# Top.net
KiCad netlist of a schematic drawn in Altium Designer
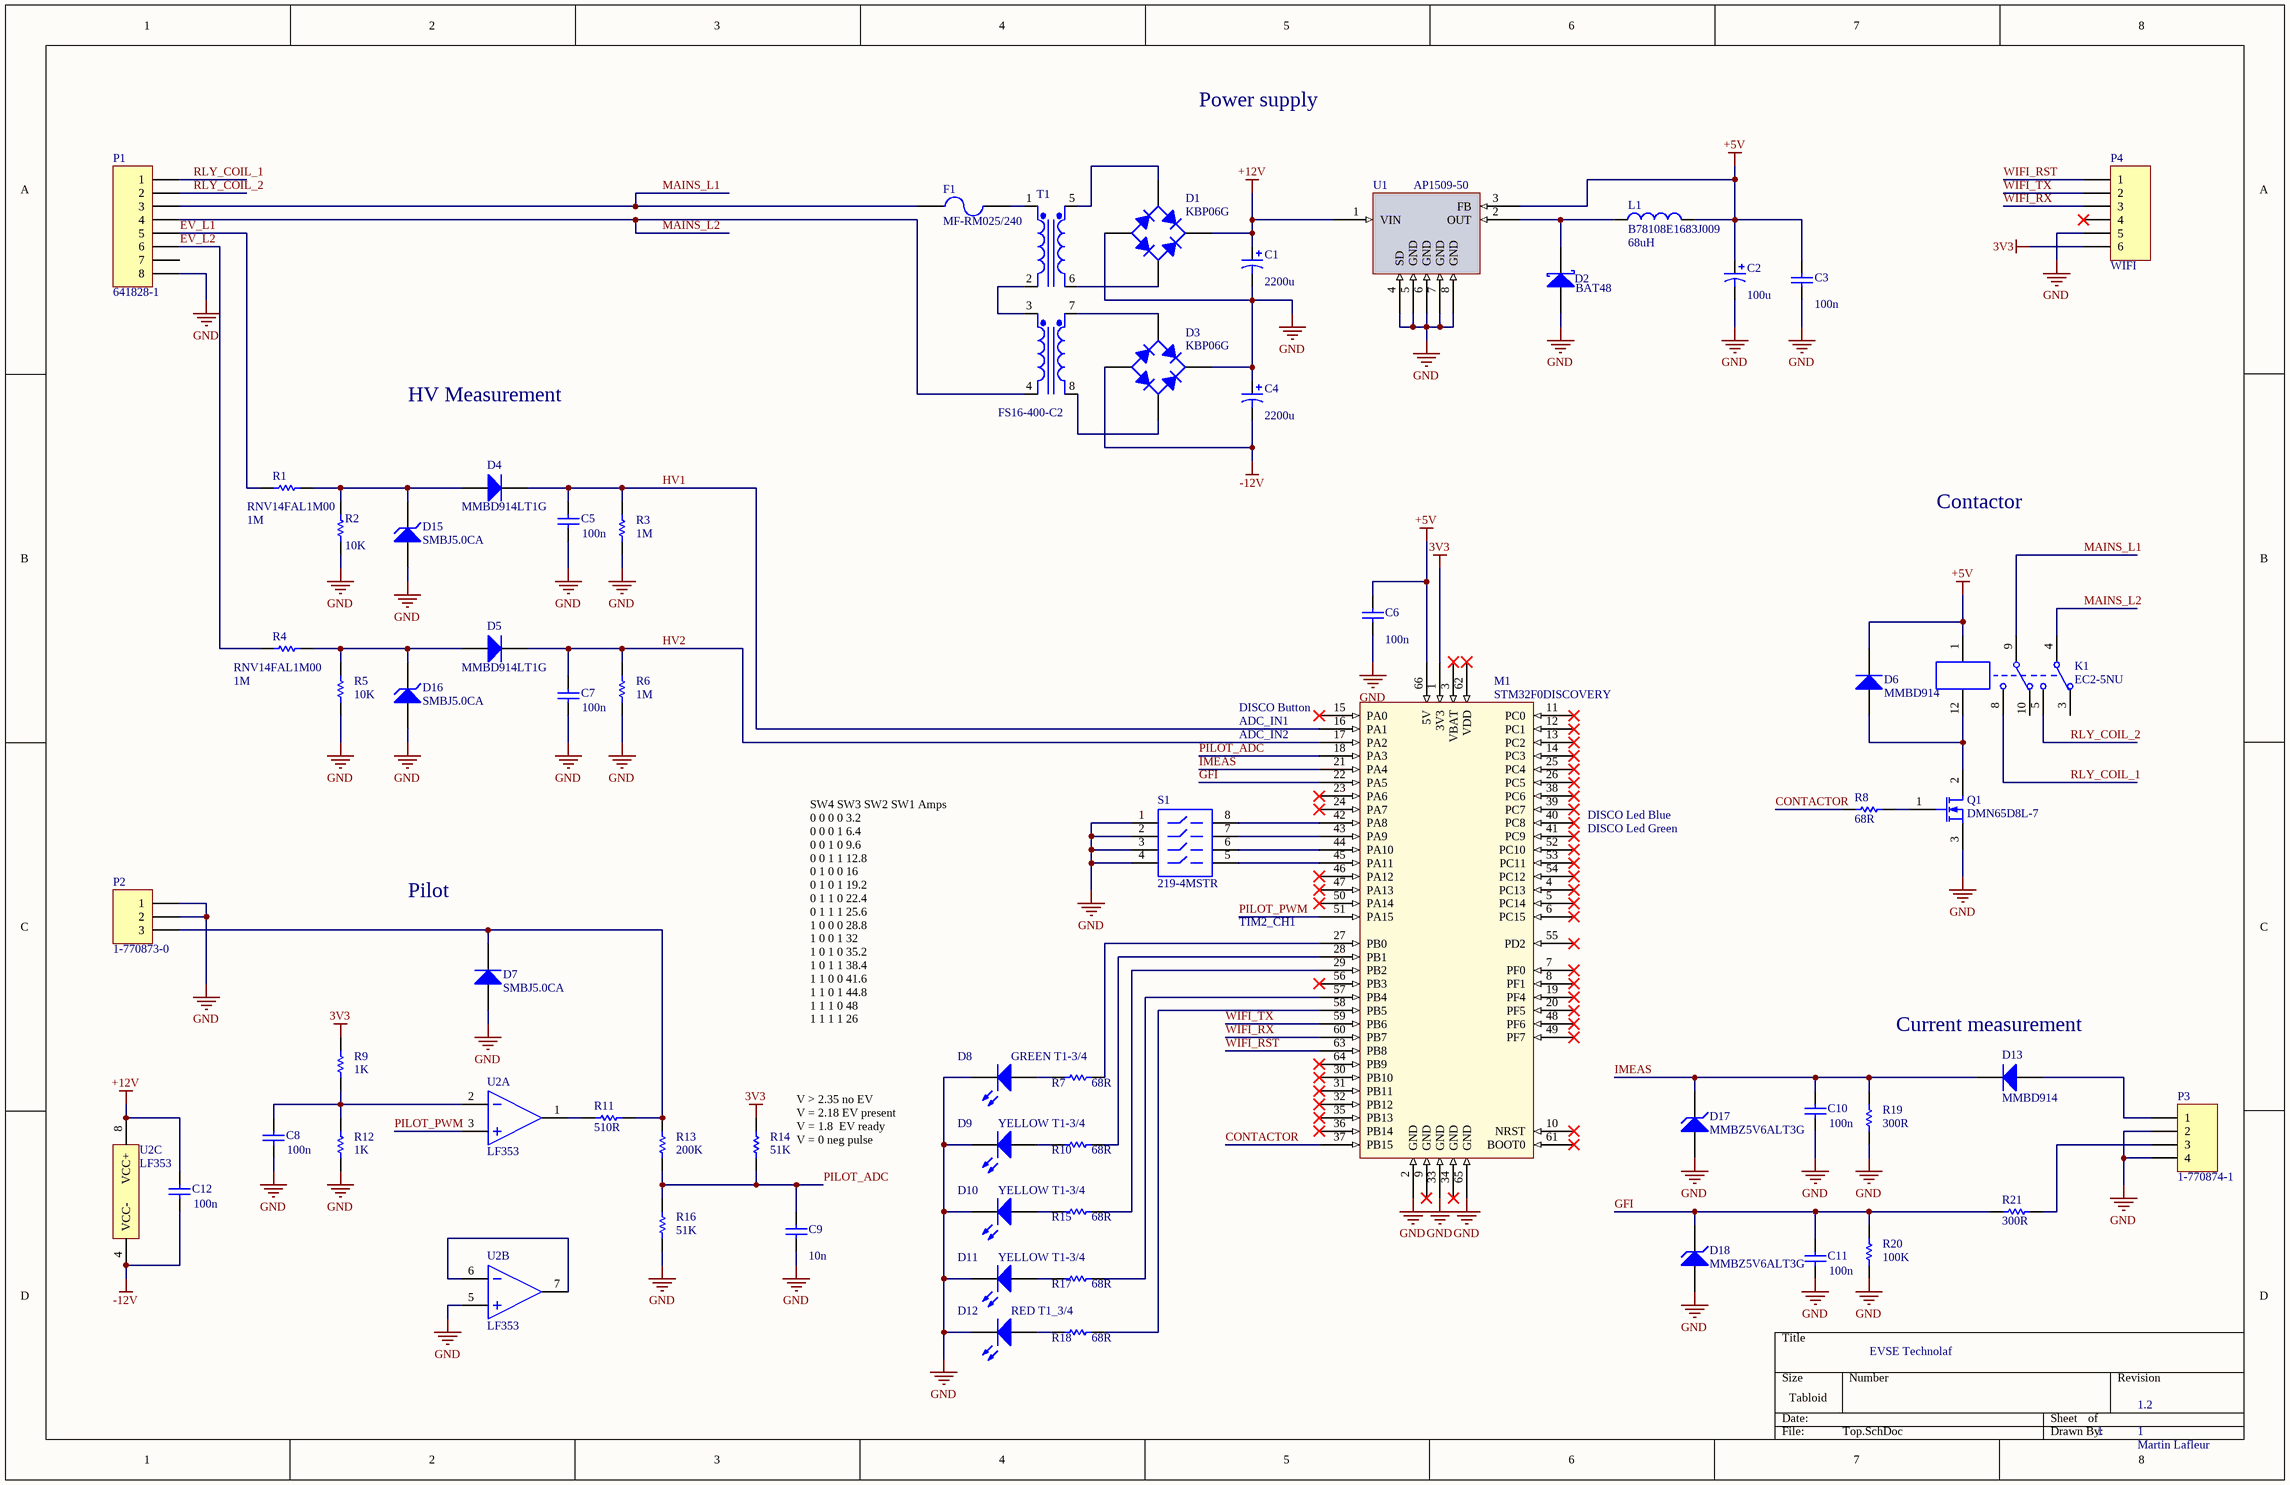
[diagram p0: Top.SchDoc]

(export (version "E")
  (design (tool "Eeschema 10.0.6"))
  (components
    (comp (ref "C1")
      (value "2200u")
      (footprint "RB7.6-15")
      (description "Polarized Capacitor (Radial)")
      (fields (field (name "Comment") "Cap Pol1") (field (name "PUBLISHER") "Altium Limited"))
      (libsource (lib "Miscellaneous Devices") (part "Cap Pol1"))
    )
    (comp (ref "C2")
      (value "100u")
      (footprint "RB0.1")
      (description "Polarized Capacitor (Radial)")
      (fields (field (name "Comment") "Cap Pol1") (field (name "PUBLISHER") "Altium Limited"))
      (libsource (lib "Miscellaneous Devices") (part "Cap Pol1"))
    )
    (comp (ref "C3")
      (value "100n")
      (footprint "6-0805_M")
      (description "Capacitor")
      (fields (field (name "Comment") "Cap") (field (name "PUBLISHER") "Altium Limited"))
      (libsource (lib "Miscellaneous Devices") (part "Cap"))
    )
    (comp (ref "C4")
      (value "2200u")
      (footprint "RB7.6-15")
      (description "Polarized Capacitor (Radial)")
      (fields (field (name "PUBLISHER") "Altium Limited"))
      (libsource (lib "Miscellaneous Devices") (part "Cap Pol1"))
    )
    (comp (ref "C5")
      (value "100n")
      (footprint "6-0805_M")
      (description "Capacitor")
      (fields (field (name "Comment") "Cap") (field (name "PUBLISHER") "Altium Limited"))
      (libsource (lib "Miscellaneous Devices") (part "Cap"))
    )
    (comp (ref "C6")
      (value "100n")
      (footprint "6-0805_M")
      (description "Capacitor")
      (fields (field (name "Comment") "Cap") (field (name "PUBLISHER") "Altium Limited"))
      (libsource (lib "Miscellaneous Devices") (part "Cap"))
    )
    (comp (ref "C7")
      (value "100n")
      (footprint "6-0805_M")
      (description "Capacitor")
      (fields (field (name "Comment") "Cap") (field (name "PUBLISHER") "Altium Limited"))
      (libsource (lib "Miscellaneous Devices") (part "Cap"))
    )
    (comp (ref "C8")
      (value "100n")
      (footprint "6-0805_M")
      (description "Capacitor")
      (fields (field (name "Comment") "Cap") (field (name "PUBLISHER") "Altium Limited"))
      (libsource (lib "Miscellaneous Devices") (part "Cap"))
    )
    (comp (ref "C9")
      (value "10n")
      (footprint "6-0805_M")
      (description "Capacitor")
      (fields (field (name "Comment") "Cap") (field (name "PUBLISHER") "Altium Limited"))
      (libsource (lib "Miscellaneous Devices") (part "Cap"))
    )
    (comp (ref "C10")
      (value "100n")
      (footprint "6-0805_M")
      (description "Capacitor")
      (fields (field (name "Comment") "Cap") (field (name "PUBLISHER") "Altium Limited"))
      (libsource (lib "Miscellaneous Devices") (part "Cap"))
    )
    (comp (ref "C11")
      (value "100n")
      (footprint "6-0805_M")
      (description "Capacitor")
      (fields (field (name "Comment") "Cap") (field (name "PUBLISHER") "Altium Limited"))
      (libsource (lib "Miscellaneous Devices") (part "Cap"))
    )
    (comp (ref "C12")
      (value "100n")
      (footprint "6-0805_M")
      (description "Capacitor")
      (fields (field (name "Comment") "Cap") (field (name "PUBLISHER") "Altium Limited"))
      (libsource (lib "Miscellaneous Devices") (part "Cap"))
    )
    (comp (ref "D1")
      (value "KBP06G")
      (footprint "KBP06M")
      (description "Full Wave Diode Bridge")
      (fields (field (name "PUBLISHER") "Altium Limited"))
      (libsource (lib "Miscellaneous Devices") (part "Bridge1"))
    )
    (comp (ref "D2")
      (value "BAT48")
      (footprint "AXIAL-0.6")
      (description "Schottky Diode")
      (fields (field (name "PUBLISHER") "Altium Limited"))
      (libsource (lib "Miscellaneous Devices") (part "D Schottky"))
    )
    (comp (ref "D3")
      (value "KBP06G")
      (footprint "KBP06M")
      (description "Full Wave Diode Bridge")
      (fields (field (name "PUBLISHER") "Altium Limited"))
      (libsource (lib "Miscellaneous Devices") (part "Bridge1"))
    )
    (comp (ref "D4")
      (value "MMBD914LT1G")
      (footprint "SOT23_914")
      (description "Default Diode")
      (fields (field (name "PUBLISHER") "Altium Limited"))
      (libsource (lib "Miscellaneous Devices") (part "Diode"))
    )
    (comp (ref "D5")
      (value "MMBD914LT1G")
      (footprint "SOT23_914")
      (description "Default Diode")
      (fields (field (name "PUBLISHER") "Altium Limited"))
      (libsource (lib "Miscellaneous Devices") (part "Diode"))
    )
    (comp (ref "D6")
      (value "MMBD914")
      (footprint "SOT23_914")
      (description "Default Diode")
      (fields (field (name "PUBLISHER") "Altium Limited"))
      (libsource (lib "Miscellaneous Devices") (part "Diode"))
    )
    (comp (ref "D7")
      (value "SMBJ5.0CA")
      (footprint "SMB")
      (description "Default Diode")
      (fields (field (name "PUBLISHER") "Altium Limited"))
      (libsource (lib "Miscellaneous Devices") (part "Diode"))
    )
    (comp (ref "D8")
      (value "GREEN T1-3/4")
      (footprint "LED_T13/4")
      (description "Typical INFRARED GaAs LED")
      (fields (field (name "PUBLISHER") "Altium Limited"))
      (libsource (lib "Miscellaneous Devices") (part "LED0"))
    )
    (comp (ref "D9")
      (value "YELLOW T1-3/4")
      (footprint "LED_T13/4")
      (description "Typical INFRARED GaAs LED")
      (fields (field (name "PUBLISHER") "Altium Limited"))
      (libsource (lib "Miscellaneous Devices") (part "LED0"))
    )
    (comp (ref "D10")
      (value "YELLOW T1-3/4")
      (footprint "LED_T13/4")
      (description "Typical INFRARED GaAs LED")
      (fields (field (name "PUBLISHER") "Altium Limited"))
      (libsource (lib "Miscellaneous Devices") (part "LED0"))
    )
    (comp (ref "D11")
      (value "YELLOW T1-3/4")
      (footprint "LED_T13/4")
      (description "Typical INFRARED GaAs LED")
      (fields (field (name "PUBLISHER") "Altium Limited"))
      (libsource (lib "Miscellaneous Devices") (part "LED0"))
    )
    (comp (ref "D12")
      (value "RED T1_3/4")
      (footprint "LED_T13/4")
      (description "RED")
      (fields (field (name "PUBLISHER") "Altium Limited"))
      (libsource (lib "Miscellaneous Devices") (part "LED0"))
    )
    (comp (ref "D13")
      (value "MMBD914")
      (footprint "SOT23_914")
      (description "Default Diode")
      (fields (field (name "PUBLISHER") "Altium Limited"))
      (libsource (lib "Miscellaneous Devices") (part "Diode"))
    )
    (comp (ref "D15")
      (value "SMBJ5.0CA")
      (footprint "SMB")
      (description "Zener Diode")
      (fields (field (name "PUBLISHER") "Altium Limited"))
      (libsource (lib "Miscellaneous Devices") (part "D Zener"))
    )
    (comp (ref "D16")
      (value "SMBJ5.0CA")
      (footprint "SMB")
      (description "Zener Diode")
      (fields (field (name "PUBLISHER") "Altium Limited"))
      (libsource (lib "Miscellaneous Devices") (part "D Zener"))
    )
    (comp (ref "D17")
      (value "MMBZ5V6ALT3G")
      (footprint "SOT23_914")
      (description "Zener Diode")
      (fields (field (name "PUBLISHER") "Altium Limited"))
      (libsource (lib "Miscellaneous Devices") (part "D Zener"))
    )
    (comp (ref "D18")
      (value "MMBZ5V6ALT3G")
      (footprint "SOT23_914")
      (description "Zener Diode")
      (fields (field (name "PUBLISHER") "Altium Limited"))
      (libsource (lib "Miscellaneous Devices") (part "D Zener"))
    )
    (comp (ref "F1")
      (value "MF-RM025/240")
      (footprint "MF-RM025/240")
      (description "MF-RM025/240-2")
      (fields (field (name "PUBLISHER") "Altium Limited"))
      (libsource (lib "Miscellaneous Devices") (part "Fuse 2"))
    )
    (comp (ref "K1")
      (value "EC2-5NU")
      (footprint "EC2-5NU")
      (description "Dual-Pole Dual-Throw Relay")
      (fields (field (name "PUBLISHER") "Altium Limited"))
      (libsource (lib "laf") (part "Relay-DPDT"))
    )
    (comp (ref "L1")
      (value "B78108E1683J009")
      (footprint "AXIAL-0.6")
      (description "Inductor")
      (fields (field (name "ALTIUM_VALUE") "68uH") (field (name "PUBLISHER") "Altium Limited"))
      (libsource (lib "Miscellaneous Devices") (part "Inductor"))
    )
    (comp (ref "M1")
      (value "STM32F0DISCOVERY")
      (footprint "laf:STM32F0DISCO")
      (libsource (lib "laf") (part "STM32F0DISCOVERY"))
    )
    (comp (ref "P1")
      (value "641828-1")
      (footprint "641828-1")
      (description "Header, 8-Pin")
      (fields (field (name "PUBLISHER") "Altium Limited"))
      (libsource (lib "Miscellaneous Connectors") (part "Header 8"))
    )
    (comp (ref "P2")
      (value "1-770873-0")
      (footprint "MATENLOK_1X3")
      (description "Header, 3-Pin")
      (fields (field (name "PUBLISHER") "Altium Limited"))
      (libsource (lib "Miscellaneous Connectors") (part "Header 3"))
    )
    (comp (ref "P3")
      (value "1-770874-1")
      (footprint "MATENLOK_2X2")
      (description "Header, 4-Pin")
      (fields (field (name "PUBLISHER") "Altium Limited"))
      (libsource (lib "Miscellaneous Connectors") (part "Header 4"))
    )
    (comp (ref "P4")
      (value "WIFI")
      (footprint "HDR1X6")
      (description "Header, 6-Pin")
      (fields (field (name "PUBLISHER") "Altium Limited"))
      (libsource (lib "Miscellaneous Connectors") (part "Header 6"))
    )
    (comp (ref "Q1")
      (value "DMN65D8L-7")
      (description "N-Channel MOSFET")
      (fields (field (name "PUBLISHER") "Altium Limited"))
      (libsource (lib "laf") (part "MOSFET-N"))
    )
    (comp (ref "R1")
      (value "RNV14FAL1M00")
      (footprint "AXIAL-0.6")
      (description "Resistor")
      (fields (field (name "ALTIUM_VALUE") "1M") (field (name "PUBLISHER") "Altium Limited"))
      (libsource (lib "Miscellaneous Devices") (part "Res1"))
    )
    (comp (ref "R2")
      (value "10K")
      (footprint "6-0805_M")
      (description "Resistor")
      (fields (field (name "Comment") "Res1") (field (name "PUBLISHER") "Altium Limited"))
      (libsource (lib "Miscellaneous Devices") (part "Res1"))
    )
    (comp (ref "R3")
      (value "1M")
      (footprint "6-0805_M")
      (description "Resistor")
      (fields (field (name "Comment") "Res1") (field (name "PUBLISHER") "Altium Limited"))
      (libsource (lib "Miscellaneous Devices") (part "Res1"))
    )
    (comp (ref "R4")
      (value "RNV14FAL1M00")
      (footprint "AXIAL-0.6")
      (description "Resistor")
      (fields (field (name "ALTIUM_VALUE") "1M") (field (name "PUBLISHER") "Altium Limited"))
      (libsource (lib "Miscellaneous Devices") (part "Res1"))
    )
    (comp (ref "R5")
      (value "10K")
      (footprint "6-0805_M")
      (description "Resistor")
      (fields (field (name "Comment") "Res1") (field (name "PUBLISHER") "Altium Limited"))
      (libsource (lib "Miscellaneous Devices") (part "Res1"))
    )
    (comp (ref "R6")
      (value "1M")
      (footprint "6-0805_M")
      (description "Resistor")
      (fields (field (name "Comment") "Res1") (field (name "PUBLISHER") "Altium Limited"))
      (libsource (lib "Miscellaneous Devices") (part "Res1"))
    )
    (comp (ref "R7")
      (value "68R")
      (footprint "6-0805_M")
      (description "Resistor")
      (fields (field (name "Comment") "Res1") (field (name "PUBLISHER") "Altium Limited"))
      (libsource (lib "Miscellaneous Devices") (part "Res1"))
    )
    (comp (ref "R8")
      (value "68R")
      (footprint "6-0805_M")
      (description "Resistor")
      (fields (field (name "Comment") "Res1") (field (name "PUBLISHER") "Altium Limited"))
      (libsource (lib "Miscellaneous Devices") (part "Res1"))
    )
    (comp (ref "R9")
      (value "1K")
      (footprint "6-0805_M")
      (description "Resistor")
      (fields (field (name "Comment") "Res1") (field (name "PUBLISHER") "Altium Limited"))
      (libsource (lib "Miscellaneous Devices") (part "Res1"))
    )
    (comp (ref "R10")
      (value "68R")
      (footprint "6-0805_M")
      (description "Resistor")
      (fields (field (name "Comment") "Res1") (field (name "PUBLISHER") "Altium Limited"))
      (libsource (lib "Miscellaneous Devices") (part "Res1"))
    )
    (comp (ref "R11")
      (value "510R")
      (footprint "6-0805_M")
      (description "Resistor")
      (fields (field (name "Comment") "Res1") (field (name "PUBLISHER") "Altium Limited"))
      (libsource (lib "Miscellaneous Devices") (part "Res1"))
    )
    (comp (ref "R12")
      (value "1K")
      (footprint "6-0805_M")
      (description "Resistor")
      (fields (field (name "Comment") "Res1") (field (name "PUBLISHER") "Altium Limited"))
      (libsource (lib "Miscellaneous Devices") (part "Res1"))
    )
    (comp (ref "R13")
      (value "200K")
      (footprint "6-0805_M")
      (description "Resistor")
      (fields (field (name "Comment") "Res1") (field (name "PUBLISHER") "Altium Limited"))
      (libsource (lib "Miscellaneous Devices") (part "Res1"))
    )
    (comp (ref "R14")
      (value "51K")
      (footprint "6-0805_M")
      (description "Resistor")
      (fields (field (name "Comment") "Res1") (field (name "PUBLISHER") "Altium Limited"))
      (libsource (lib "Miscellaneous Devices") (part "Res1"))
    )
    (comp (ref "R15")
      (value "68R")
      (footprint "6-0805_M")
      (description "Resistor")
      (fields (field (name "Comment") "Res1") (field (name "PUBLISHER") "Altium Limited"))
      (libsource (lib "Miscellaneous Devices") (part "Res1"))
    )
    (comp (ref "R16")
      (value "51K")
      (footprint "6-0805_M")
      (description "Resistor")
      (fields (field (name "Comment") "Res1") (field (name "PUBLISHER") "Altium Limited"))
      (libsource (lib "Miscellaneous Devices") (part "Res1"))
    )
    (comp (ref "R17")
      (value "68R")
      (footprint "6-0805_M")
      (description "Resistor")
      (fields (field (name "Comment") "Res1") (field (name "PUBLISHER") "Altium Limited"))
      (libsource (lib "Miscellaneous Devices") (part "Res1"))
    )
    (comp (ref "R18")
      (value "68R")
      (footprint "6-0805_M")
      (description "Resistor")
      (fields (field (name "Comment") "Res1") (field (name "PUBLISHER") "Altium Limited"))
      (libsource (lib "Miscellaneous Devices") (part "Res1"))
    )
    (comp (ref "R19")
      (value "300R")
      (footprint "6-0805_M")
      (description "Resistor")
      (fields (field (name "Comment") "Res1") (field (name "PUBLISHER") "Altium Limited"))
      (libsource (lib "Miscellaneous Devices") (part "Res1"))
    )
    (comp (ref "R20")
      (value "100K")
      (footprint "6-0805_M")
      (description "Resistor")
      (fields (field (name "Comment") "Res1") (field (name "PUBLISHER") "Altium Limited"))
      (libsource (lib "Miscellaneous Devices") (part "Res1"))
    )
    (comp (ref "R21")
      (value "300R")
      (footprint "6-0805_M")
      (description "Resistor")
      (fields (field (name "Comment") "Res1") (field (name "PUBLISHER") "Altium Limited"))
      (libsource (lib "Miscellaneous Devices") (part "Res1"))
    )
    (comp (ref "S1")
      (value "219-4MSTR")
      (footprint "DIPSW4")
      (description "DIP Switch")
      (fields (field (name "PUBLISHER") "Altium Limited"))
      (libsource (lib "Miscellaneous Devices") (part "SW-DIP4"))
    )
    (comp (ref "T1")
      (value "FS16-400-C2")
      (footprint "FS16-400-C2")
      (libsource (lib "laf") (part "TRANSFO_2p2s"))
    )
    (comp (ref "U1") (value "AP1509-50") (footprint "SO8_N") (libsource (lib "laf") (part "AP1509")))
    (comp (ref "U2")
      (value "LF353")
      (footprint "SO8_N")
      (description "IC OPAMP GP 700KHZ 8DIP")
      (fields
        (field (name "MANUFACTURER") "Texas Instruments")
        (field (name "MANUFACTURER PART NUMBER") "LM358P")
      )
      (libsource (lib "GRR_IC") (part "LM358P"))
    )
  )
  (nets
    (net (code "1") (name "+5V") (class "Default")
      (node (ref "C2") (pin "1") (pinfunction "1_1") (pintype "passive"))
      (node (ref "C3") (pin "2") (pinfunction "2_2") (pintype "passive"))
      (node (ref "C6") (pin "2") (pinfunction "2_2") (pintype "passive"))
      (node (ref "D6") (pin "2") (pinfunction "K_2") (pintype "passive"))
      (node (ref "K1") (pin "1") (pinfunction "1_1") (pintype "passive"))
      (node (ref "L1") (pin "2") (pinfunction "2_2") (pintype "passive"))
      (node (ref "M1") (pin "66") (pinfunction "5V_66") (pintype "input"))
      (node (ref "U1") (pin "3") (pinfunction "FB_3") (pintype "input"))
    )
    (net (code "2") (name "+12V") (class "Default")
      (node (ref "C1") (pin "1") (pinfunction "1_1") (pintype "passive"))
      (node (ref "C12") (pin "2") (pinfunction "2_2") (pintype "passive"))
      (node (ref "D1") (pin "1") (pinfunction "K_1") (pintype "passive"))
      (node (ref "U1") (pin "1") (pinfunction "VIN_1") (pintype "input"))
      (node (ref "U2") (pin "8") (pinfunction "VCC+_8") (pintype "power_in"))
    )
    (net (code "3") (name "-12V") (class "Default")
      (node (ref "C12") (pin "1") (pinfunction "1_1") (pintype "passive"))
      (node (ref "C4") (pin "2") (pinfunction "2_2") (pintype "passive"))
      (node (ref "D3") (pin "3") (pinfunction "A_3") (pintype "passive"))
      (node (ref "U2") (pin "4") (pinfunction "VCC-_4") (pintype "power_in"))
    )
    (net (code "4") (name "/CONTACTOR") (class "Default")
      (node (ref "M1") (pin "37") (pinfunction "PB15_37") (pintype "input"))
      (node (ref "R8") (pin "2") (pinfunction "2_2") (pintype "passive"))
    )
    (net (code "5") (name "/EV_L1") (class "Default")
      (node (ref "P1") (pin "5") (pinfunction "5_5") (pintype "passive"))
      (node (ref "R1") (pin "2") (pinfunction "2_2") (pintype "passive"))
    )
    (net (code "6") (name "/EV_L2") (class "Default")
      (node (ref "P1") (pin "6") (pinfunction "6_6") (pintype "passive"))
      (node (ref "R4") (pin "2") (pinfunction "2_2") (pintype "passive"))
    )
    (net (code "7") (name "/GFI") (class "Default")
      (node (ref "C11") (pin "2") (pinfunction "2_2") (pintype "passive"))
      (node (ref "D18") (pin "2") (pinfunction "K_2") (pintype "passive"))
      (node (ref "M1") (pin "22") (pinfunction "PA5_22") (pintype "input"))
      (node (ref "R20") (pin "2") (pinfunction "2_2") (pintype "passive"))
      (node (ref "R21") (pin "2") (pinfunction "2_2") (pintype "passive"))
    )
    (net (code "8") (name "/HV1") (class "Default")
      (node (ref "C5") (pin "2") (pinfunction "2_2") (pintype "passive"))
      (node (ref "D4") (pin "2") (pinfunction "K_2") (pintype "passive"))
      (node (ref "M1") (pin "16") (pinfunction "PA1_16") (pintype "input"))
      (node (ref "R3") (pin "2") (pinfunction "2_2") (pintype "passive"))
    )
    (net (code "9") (name "/HV2") (class "Default")
      (node (ref "C7") (pin "2") (pinfunction "2_2") (pintype "passive"))
      (node (ref "D5") (pin "2") (pinfunction "K_2") (pintype "passive"))
      (node (ref "M1") (pin "17") (pinfunction "PA2_17") (pintype "input"))
      (node (ref "R6") (pin "2") (pinfunction "2_2") (pintype "passive"))
    )
    (net (code "10") (name "/IMEAS") (class "Default")
      (node (ref "C10") (pin "2") (pinfunction "2_2") (pintype "passive"))
      (node (ref "D13") (pin "2") (pinfunction "K_2") (pintype "passive"))
      (node (ref "D17") (pin "2") (pinfunction "K_2") (pintype "passive"))
      (node (ref "M1") (pin "21") (pinfunction "PA4_21") (pintype "input"))
      (node (ref "R19") (pin "2") (pinfunction "2_2") (pintype "passive"))
    )
    (net (code "11") (name "/MAINS_L1") (class "Default")
      (node (ref "F1") (pin "1") (pinfunction "1_1") (pintype "passive"))
      (node (ref "K1") (pin "9") (pinfunction "9_9") (pintype "passive"))
      (node (ref "P1") (pin "3") (pinfunction "3_3") (pintype "passive"))
    )
    (net (code "12") (name "/MAINS_L2") (class "Default")
      (node (ref "K1") (pin "4") (pinfunction "4_4") (pintype "passive"))
      (node (ref "P1") (pin "4") (pinfunction "4_4") (pintype "passive"))
      (node (ref "T1") (pin "4") (pinfunction "Pri2-_4") (pintype "passive"))
    )
    (net (code "13") (name "/PILOT_ADC") (class "Default")
      (node (ref "C9") (pin "2") (pinfunction "2_2") (pintype "passive"))
      (node (ref "M1") (pin "18") (pinfunction "PA3_18") (pintype "input"))
      (node (ref "R13") (pin "1") (pinfunction "1_1") (pintype "passive"))
      (node (ref "R14") (pin "1") (pinfunction "1_1") (pintype "passive"))
      (node (ref "R16") (pin "2") (pinfunction "2_2") (pintype "passive"))
    )
    (net (code "14") (name "/PILOT_PWM") (class "Default")
      (node (ref "M1") (pin "51") (pinfunction "PA15_51") (pintype "input"))
      (node (ref "U2") (pin "3") (pinfunction "IN+_3") (pintype "passive"))
    )
    (net (code "15") (name "/RLY_COIL_1") (class "Default")
      (node (ref "K1") (pin "8") (pinfunction "8_8") (pintype "passive"))
      (node (ref "P1") (pin "1") (pinfunction "1_1") (pintype "passive"))
    )
    (net (code "16") (name "/RLY_COIL_2") (class "Default")
      (node (ref "K1") (pin "5") (pinfunction "5_5") (pintype "passive"))
      (node (ref "P1") (pin "2") (pinfunction "2_2") (pintype "passive"))
    )
    (net (code "17") (name "/WIFI_RST") (class "Default")
      (node (ref "M1") (pin "63") (pinfunction "PB8_63") (pintype "input"))
      (node (ref "P4") (pin "1") (pinfunction "1_1") (pintype "passive"))
    )
    (net (code "18") (name "/WIFI_RX") (class "Default")
      (node (ref "M1") (pin "60") (pinfunction "PB7_60") (pintype "input"))
      (node (ref "P4") (pin "3") (pinfunction "3_3") (pintype "passive"))
    )
    (net (code "19") (name "/WIFI_TX") (class "Default")
      (node (ref "M1") (pin "59") (pinfunction "PB6_59") (pintype "input"))
      (node (ref "P4") (pin "2") (pinfunction "2_2") (pintype "passive"))
    )
    (net (code "20") (name "3V3") (class "Default")
      (node (ref "M1") (pin "1") (pinfunction "3V3_1") (pintype "input"))
      (node (ref "P4") (pin "6") (pinfunction "6_6") (pintype "passive"))
      (node (ref "R14") (pin "2") (pinfunction "2_2") (pintype "passive"))
      (node (ref "R9") (pin "2") (pinfunction "2_2") (pintype "passive"))
    )
    (net (code "21") (name "GND") (class "Default")
      (node (ref "C1") (pin "2") (pinfunction "2_2") (pintype "passive"))
      (node (ref "C10") (pin "1") (pinfunction "1_1") (pintype "passive"))
      (node (ref "C11") (pin "1") (pinfunction "1_1") (pintype "passive"))
      (node (ref "C2") (pin "2") (pinfunction "2_2") (pintype "passive"))
      (node (ref "C3") (pin "1") (pinfunction "1_1") (pintype "passive"))
      (node (ref "C4") (pin "1") (pinfunction "1_1") (pintype "passive"))
      (node (ref "C5") (pin "1") (pinfunction "1_1") (pintype "passive"))
      (node (ref "C6") (pin "1") (pinfunction "1_1") (pintype "passive"))
      (node (ref "C7") (pin "1") (pinfunction "1_1") (pintype "passive"))
      (node (ref "C8") (pin "1") (pinfunction "1_1") (pintype "passive"))
      (node (ref "C9") (pin "1") (pinfunction "1_1") (pintype "passive"))
      (node (ref "D1") (pin "3") (pinfunction "A_3") (pintype "passive"))
      (node (ref "D10") (pin "2") (pinfunction "K_2") (pintype "passive"))
      (node (ref "D11") (pin "2") (pinfunction "K_2") (pintype "passive"))
      (node (ref "D12") (pin "2") (pinfunction "K_2") (pintype "passive"))
      (node (ref "D15") (pin "1") (pinfunction "A_1") (pintype "passive"))
      (node (ref "D16") (pin "1") (pinfunction "A_1") (pintype "passive"))
      (node (ref "D17") (pin "1") (pinfunction "A_1") (pintype "passive"))
      (node (ref "D18") (pin "1") (pinfunction "A_1") (pintype "passive"))
      (node (ref "D2") (pin "1") (pinfunction "A_1") (pintype "passive"))
      (node (ref "D3") (pin "1") (pinfunction "K_1") (pintype "passive"))
      (node (ref "D7") (pin "1") (pinfunction "A_1") (pintype "passive"))
      (node (ref "D8") (pin "2") (pinfunction "K_2") (pintype "passive"))
      (node (ref "D9") (pin "2") (pinfunction "K_2") (pintype "passive"))
      (node (ref "M1") (pin "2") (pinfunction "GND_2") (pintype "input"))
      (node (ref "M1") (pin "33") (pinfunction "GND_33") (pintype "input"))
      (node (ref "M1") (pin "65") (pinfunction "GND_65") (pintype "input"))
      (node (ref "P1") (pin "8") (pinfunction "8_8") (pintype "passive"))
      (node (ref "P2") (pin "1") (pinfunction "1_1") (pintype "passive"))
      (node (ref "P2") (pin "2") (pinfunction "2_2") (pintype "passive"))
      (node (ref "P3") (pin "2") (pinfunction "2_2") (pintype "passive"))
      (node (ref "P3") (pin "4") (pinfunction "4_4") (pintype "passive"))
      (node (ref "P4") (pin "5") (pinfunction "5_5") (pintype "passive"))
      (node (ref "Q1") (pin "3") (pinfunction "S_3") (pintype "passive"))
      (node (ref "R12") (pin "1") (pinfunction "1_1") (pintype "passive"))
      (node (ref "R16") (pin "1") (pinfunction "1_1") (pintype "passive"))
      (node (ref "R19") (pin "1") (pinfunction "1_1") (pintype "passive"))
      (node (ref "R2") (pin "1") (pinfunction "1_1") (pintype "passive"))
      (node (ref "R20") (pin "1") (pinfunction "1_1") (pintype "passive"))
      (node (ref "R3") (pin "1") (pinfunction "1_1") (pintype "passive"))
      (node (ref "R5") (pin "1") (pinfunction "1_1") (pintype "passive"))
      (node (ref "R6") (pin "1") (pinfunction "1_1") (pintype "passive"))
      (node (ref "S1") (pin "1") (pinfunction "1_1") (pintype "passive"))
      (node (ref "S1") (pin "2") (pinfunction "2_2") (pintype "passive"))
      (node (ref "S1") (pin "3") (pinfunction "3_3") (pintype "passive"))
      (node (ref "S1") (pin "4") (pinfunction "4_4") (pintype "passive"))
      (node (ref "U1") (pin "4") (pinfunction "SD_4") (pintype "input"))
      (node (ref "U1") (pin "5") (pinfunction "GND_5") (pintype "input"))
      (node (ref "U1") (pin "6") (pinfunction "GND_6") (pintype "input"))
      (node (ref "U1") (pin "7") (pinfunction "GND_7") (pintype "input"))
      (node (ref "U1") (pin "8") (pinfunction "GND_8") (pintype "input"))
      (node (ref "U2") (pin "5") (pinfunction "IN+_5") (pintype "passive"))
    )
    (net (code "22") (name "Net-(D2-K)") (class "Default")
      (node (ref "D2") (pin "2") (pinfunction "K_2") (pintype "passive"))
      (node (ref "L1") (pin "1") (pinfunction "1_1") (pintype "passive"))
      (node (ref "U1") (pin "2") (pinfunction "OUT_2") (pintype "input"))
    )
    (net (code "23") (name "Net-(D6-A)") (class "Default")
      (node (ref "D6") (pin "1") (pinfunction "A_1") (pintype "passive"))
      (node (ref "K1") (pin "12") (pinfunction "12_12") (pintype "passive"))
      (node (ref "Q1") (pin "2") (pinfunction "D_2") (pintype "passive"))
    )
    (net (code "24") (name "Net-(D7-K)") (class "Default")
      (node (ref "D7") (pin "2") (pinfunction "K_2") (pintype "passive"))
      (node (ref "P2") (pin "3") (pinfunction "3_3") (pintype "passive"))
      (node (ref "R11") (pin "1") (pinfunction "1_1") (pintype "passive"))
      (node (ref "R13") (pin "2") (pinfunction "2_2") (pintype "passive"))
    )
    (net (code "25") (name "Net-(D8-A)") (class "Default")
      (node (ref "D8") (pin "1") (pinfunction "A_1") (pintype "passive"))
      (node (ref "R7") (pin "2") (pinfunction "2_2") (pintype "passive"))
    )
    (net (code "26") (name "Net-(D9-A)") (class "Default")
      (node (ref "D9") (pin "1") (pinfunction "A_1") (pintype "passive"))
      (node (ref "R10") (pin "2") (pinfunction "2_2") (pintype "passive"))
    )
    (net (code "27") (name "Net-(D10-A)") (class "Default")
      (node (ref "D10") (pin "1") (pinfunction "A_1") (pintype "passive"))
      (node (ref "R15") (pin "2") (pinfunction "2_2") (pintype "passive"))
    )
    (net (code "28") (name "Net-(D11-A)") (class "Default")
      (node (ref "D11") (pin "1") (pinfunction "A_1") (pintype "passive"))
      (node (ref "R17") (pin "2") (pinfunction "2_2") (pintype "passive"))
    )
    (net (code "29") (name "Net-(D12-A)") (class "Default")
      (node (ref "D12") (pin "1") (pinfunction "A_1") (pintype "passive"))
      (node (ref "R18") (pin "2") (pinfunction "2_2") (pintype "passive"))
    )
    (net (code "30") (name "Net-(D13-A)") (class "Default")
      (node (ref "D13") (pin "1") (pinfunction "A_1") (pintype "passive"))
      (node (ref "P3") (pin "1") (pinfunction "1_1") (pintype "passive"))
    )
    (net (code "31") (name "Net-(D15-K)") (class "Default")
      (node (ref "D15") (pin "2") (pinfunction "K_2") (pintype "passive"))
      (node (ref "D4") (pin "1") (pinfunction "A_1") (pintype "passive"))
      (node (ref "R1") (pin "1") (pinfunction "1_1") (pintype "passive"))
      (node (ref "R2") (pin "2") (pinfunction "2_2") (pintype "passive"))
    )
    (net (code "32") (name "Net-(D16-K)") (class "Default")
      (node (ref "D16") (pin "2") (pinfunction "K_2") (pintype "passive"))
      (node (ref "D5") (pin "1") (pinfunction "A_1") (pintype "passive"))
      (node (ref "R4") (pin "1") (pinfunction "1_1") (pintype "passive"))
      (node (ref "R5") (pin "2") (pinfunction "2_2") (pintype "passive"))
    )
    (net (code "33") (name "Net-(M1-PA8)") (class "Default")
      (node (ref "M1") (pin "42") (pinfunction "PA8_42") (pintype "input"))
      (node (ref "S1") (pin "8") (pinfunction "8_8") (pintype "passive"))
    )
    (net (code "34") (name "Net-(M1-PA9)") (class "Default")
      (node (ref "M1") (pin "43") (pinfunction "PA9_43") (pintype "input"))
      (node (ref "S1") (pin "7") (pinfunction "7_7") (pintype "passive"))
    )
    (net (code "35") (name "Net-(M1-PA10)") (class "Default")
      (node (ref "M1") (pin "44") (pinfunction "PA10_44") (pintype "input"))
      (node (ref "S1") (pin "6") (pinfunction "6_6") (pintype "passive"))
    )
    (net (code "36") (name "Net-(M1-PA11)") (class "Default")
      (node (ref "M1") (pin "45") (pinfunction "PA11_45") (pintype "input"))
      (node (ref "S1") (pin "5") (pinfunction "5_5") (pintype "passive"))
    )
    (net (code "37") (name "Net-(M1-PB0)") (class "Default")
      (node (ref "M1") (pin "27") (pinfunction "PB0_27") (pintype "input"))
      (node (ref "R7") (pin "1") (pinfunction "1_1") (pintype "passive"))
    )
    (net (code "38") (name "Net-(M1-PB1)") (class "Default")
      (node (ref "M1") (pin "28") (pinfunction "PB1_28") (pintype "input"))
      (node (ref "R10") (pin "1") (pinfunction "1_1") (pintype "passive"))
    )
    (net (code "39") (name "Net-(M1-PB2)") (class "Default")
      (node (ref "M1") (pin "29") (pinfunction "PB2_29") (pintype "input"))
      (node (ref "R15") (pin "1") (pinfunction "1_1") (pintype "passive"))
    )
    (net (code "40") (name "Net-(M1-PB4)") (class "Default")
      (node (ref "M1") (pin "57") (pinfunction "PB4_57") (pintype "input"))
      (node (ref "R17") (pin "1") (pinfunction "1_1") (pintype "passive"))
    )
    (net (code "41") (name "Net-(M1-PB5)") (class "Default")
      (node (ref "M1") (pin "58") (pinfunction "PB5_58") (pintype "input"))
      (node (ref "R18") (pin "1") (pinfunction "1_1") (pintype "passive"))
    )
    (net (code "42") (name "Net-(P3-Pad3)") (class "Default")
      (node (ref "P3") (pin "3") (pinfunction "3_3") (pintype "passive"))
      (node (ref "R21") (pin "1") (pinfunction "1_1") (pintype "passive"))
    )
    (net (code "43") (name "Net-(Q1-G)") (class "Default")
      (node (ref "Q1") (pin "1") (pinfunction "G_1") (pintype "passive"))
      (node (ref "R8") (pin "1") (pinfunction "1_1") (pintype "passive"))
    )
    (net (code "44") (name "Net-(T1-Pri+)") (class "Default")
      (node (ref "F1") (pin "2") (pinfunction "2_2") (pintype "passive"))
      (node (ref "T1") (pin "1") (pinfunction "Pri+_1") (pintype "passive"))
    )
    (net (code "45") (name "Net-(T1-Pri-)") (class "Default")
      (node (ref "T1") (pin "2") (pinfunction "Pri-_2") (pintype "passive"))
      (node (ref "T1") (pin "3") (pinfunction "Pri2+_3") (pintype "passive"))
    )
    (net (code "46") (name "Net-(T1-Sec1+)") (class "Default")
      (node (ref "D1") (pin "4") (pinfunction "C_4") (pintype "passive"))
      (node (ref "T1") (pin "5") (pinfunction "Sec1+_5") (pintype "passive"))
    )
    (net (code "47") (name "Net-(T1-Sec1-)") (class "Default")
      (node (ref "D1") (pin "2") (pinfunction "C_2") (pintype "passive"))
      (node (ref "T1") (pin "6") (pinfunction "Sec1-_6") (pintype "passive"))
    )
    (net (code "48") (name "Net-(T1-Sec2+)") (class "Default")
      (node (ref "D3") (pin "4") (pinfunction "C_4") (pintype "passive"))
      (node (ref "T1") (pin "7") (pinfunction "Sec2+_7") (pintype "passive"))
    )
    (net (code "49") (name "Net-(T1-Sec2-)") (class "Default")
      (node (ref "D3") (pin "2") (pinfunction "C_2") (pintype "passive"))
      (node (ref "T1") (pin "8") (pinfunction "Sec2-_8") (pintype "passive"))
    )
    (net (code "50") (name "Net-(U2A-IN-)") (class "Default")
      (node (ref "C8") (pin "2") (pinfunction "2_2") (pintype "passive"))
      (node (ref "R12") (pin "2") (pinfunction "2_2") (pintype "passive"))
      (node (ref "R9") (pin "1") (pinfunction "1_1") (pintype "passive"))
      (node (ref "U2") (pin "2") (pinfunction "IN-_2") (pintype "passive"))
    )
    (net (code "51") (name "Net-(U2A-OUT)") (class "Default")
      (node (ref "R11") (pin "2") (pinfunction "2_2") (pintype "passive"))
      (node (ref "U2") (pin "1") (pinfunction "OUT_1") (pintype "passive"))
    )
    (net (code "52") (name "Net-(U2B-IN-)") (class "Default")
      (node (ref "U2") (pin "6") (pinfunction "IN-_6") (pintype "passive"))
      (node (ref "U2") (pin "7") (pinfunction "OUT_7") (pintype "passive"))
    )
    (net (code "53") (name "unconnected-(K1-Pad3)") (class "Default")
      (node (ref "K1") (pin "3") (pinfunction "3_3") (pintype "passive"))
    )
    (net (code "54") (name "unconnected-(K1-Pad10)") (class "Default")
      (node (ref "K1") (pin "10") (pinfunction "10_10") (pintype "passive"))
    )
    (net (code "55") (name "unconnected-(M1-BOOT0-Pad61)") (class "Default")
      (node (ref "M1") (pin "61") (pinfunction "BOOT0_61") (pintype "input+no_connect"))
    )
    (net (code "56") (name "unconnected-(M1-GND-Pad9)") (class "Default")
      (node (ref "M1") (pin "9") (pinfunction "GND_9") (pintype "input+no_connect"))
    )
    (net (code "57") (name "unconnected-(M1-GND-Pad34)") (class "Default")
      (node (ref "M1") (pin "34") (pinfunction "GND_34") (pintype "input+no_connect"))
    )
    (net (code "58") (name "unconnected-(M1-NRST-Pad10)") (class "Default")
      (node (ref "M1") (pin "10") (pinfunction "NRST_10") (pintype "input+no_connect"))
    )
    (net (code "59") (name "unconnected-(M1-PA0-Pad15)") (class "Default")
      (node (ref "M1") (pin "15") (pinfunction "PA0_15") (pintype "input+no_connect"))
    )
    (net (code "60") (name "unconnected-(M1-PA6-Pad23)") (class "Default")
      (node (ref "M1") (pin "23") (pinfunction "PA6_23") (pintype "input+no_connect"))
    )
    (net (code "61") (name "unconnected-(M1-PA7-Pad24)") (class "Default")
      (node (ref "M1") (pin "24") (pinfunction "PA7_24") (pintype "input+no_connect"))
    )
    (net (code "62") (name "unconnected-(M1-PA12-Pad46)") (class "Default")
      (node (ref "M1") (pin "46") (pinfunction "PA12_46") (pintype "input+no_connect"))
    )
    (net (code "63") (name "unconnected-(M1-PA13-Pad47)") (class "Default")
      (node (ref "M1") (pin "47") (pinfunction "PA13_47") (pintype "input+no_connect"))
    )
    (net (code "64") (name "unconnected-(M1-PA14-Pad50)") (class "Default")
      (node (ref "M1") (pin "50") (pinfunction "PA14_50") (pintype "input+no_connect"))
    )
    (net (code "65") (name "unconnected-(M1-PB3-Pad56)") (class "Default")
      (node (ref "M1") (pin "56") (pinfunction "PB3_56") (pintype "input+no_connect"))
    )
    (net (code "66") (name "unconnected-(M1-PB9-Pad64)") (class "Default")
      (node (ref "M1") (pin "64") (pinfunction "PB9_64") (pintype "input+no_connect"))
    )
    (net (code "67") (name "unconnected-(M1-PB10-Pad30)") (class "Default")
      (node (ref "M1") (pin "30") (pinfunction "PB10_30") (pintype "input+no_connect"))
    )
    (net (code "68") (name "unconnected-(M1-PB11-Pad31)") (class "Default")
      (node (ref "M1") (pin "31") (pinfunction "PB11_31") (pintype "input+no_connect"))
    )
    (net (code "69") (name "unconnected-(M1-PB12-Pad32)") (class "Default")
      (node (ref "M1") (pin "32") (pinfunction "PB12_32") (pintype "input+no_connect"))
    )
    (net (code "70") (name "unconnected-(M1-PB13-Pad35)") (class "Default")
      (node (ref "M1") (pin "35") (pinfunction "PB13_35") (pintype "input+no_connect"))
    )
    (net (code "71") (name "unconnected-(M1-PB14-Pad36)") (class "Default")
      (node (ref "M1") (pin "36") (pinfunction "PB14_36") (pintype "input+no_connect"))
    )
    (net (code "72") (name "unconnected-(M1-PC0-Pad11)") (class "Default")
      (node (ref "M1") (pin "11") (pinfunction "PC0_11") (pintype "input+no_connect"))
    )
    (net (code "73") (name "unconnected-(M1-PC1-Pad12)") (class "Default")
      (node (ref "M1") (pin "12") (pinfunction "PC1_12") (pintype "input+no_connect"))
    )
    (net (code "74") (name "unconnected-(M1-PC2-Pad13)") (class "Default")
      (node (ref "M1") (pin "13") (pinfunction "PC2_13") (pintype "input+no_connect"))
    )
    (net (code "75") (name "unconnected-(M1-PC3-Pad14)") (class "Default")
      (node (ref "M1") (pin "14") (pinfunction "PC3_14") (pintype "input+no_connect"))
    )
    (net (code "76") (name "unconnected-(M1-PC4-Pad25)") (class "Default")
      (node (ref "M1") (pin "25") (pinfunction "PC4_25") (pintype "input+no_connect"))
    )
    (net (code "77") (name "unconnected-(M1-PC5-Pad26)") (class "Default")
      (node (ref "M1") (pin "26") (pinfunction "PC5_26") (pintype "input+no_connect"))
    )
    (net (code "78") (name "unconnected-(M1-PC6-Pad38)") (class "Default")
      (node (ref "M1") (pin "38") (pinfunction "PC6_38") (pintype "input+no_connect"))
    )
    (net (code "79") (name "unconnected-(M1-PC7-Pad39)") (class "Default")
      (node (ref "M1") (pin "39") (pinfunction "PC7_39") (pintype "input+no_connect"))
    )
    (net (code "80") (name "unconnected-(M1-PC8-Pad40)") (class "Default")
      (node (ref "M1") (pin "40") (pinfunction "PC8_40") (pintype "input+no_connect"))
    )
    (net (code "81") (name "unconnected-(M1-PC9-Pad41)") (class "Default")
      (node (ref "M1") (pin "41") (pinfunction "PC9_41") (pintype "input+no_connect"))
    )
    (net (code "82") (name "unconnected-(M1-PC10-Pad52)") (class "Default")
      (node (ref "M1") (pin "52") (pinfunction "PC10_52") (pintype "input+no_connect"))
    )
    (net (code "83") (name "unconnected-(M1-PC11-Pad53)") (class "Default")
      (node (ref "M1") (pin "53") (pinfunction "PC11_53") (pintype "input+no_connect"))
    )
    (net (code "84") (name "unconnected-(M1-PC12-Pad54)") (class "Default")
      (node (ref "M1") (pin "54") (pinfunction "PC12_54") (pintype "input+no_connect"))
    )
    (net (code "85") (name "unconnected-(M1-PC13-Pad4)") (class "Default")
      (node (ref "M1") (pin "4") (pinfunction "PC13_4") (pintype "input+no_connect"))
    )
    (net (code "86") (name "unconnected-(M1-PC14-Pad5)") (class "Default")
      (node (ref "M1") (pin "5") (pinfunction "PC14_5") (pintype "input+no_connect"))
    )
    (net (code "87") (name "unconnected-(M1-PC15-Pad6)") (class "Default")
      (node (ref "M1") (pin "6") (pinfunction "PC15_6") (pintype "input+no_connect"))
    )
    (net (code "88") (name "unconnected-(M1-PD2-Pad55)") (class "Default")
      (node (ref "M1") (pin "55") (pinfunction "PD2_55") (pintype "input+no_connect"))
    )
    (net (code "89") (name "unconnected-(M1-PF0-Pad7)") (class "Default")
      (node (ref "M1") (pin "7") (pinfunction "PF0_7") (pintype "input+no_connect"))
    )
    (net (code "90") (name "unconnected-(M1-PF1-Pad8)") (class "Default")
      (node (ref "M1") (pin "8") (pinfunction "PF1_8") (pintype "input+no_connect"))
    )
    (net (code "91") (name "unconnected-(M1-PF4-Pad19)") (class "Default")
      (node (ref "M1") (pin "19") (pinfunction "PF4_19") (pintype "input+no_connect"))
    )
    (net (code "92") (name "unconnected-(M1-PF5-Pad20)") (class "Default")
      (node (ref "M1") (pin "20") (pinfunction "PF5_20") (pintype "input+no_connect"))
    )
    (net (code "93") (name "unconnected-(M1-PF6-Pad48)") (class "Default")
      (node (ref "M1") (pin "48") (pinfunction "PF6_48") (pintype "input+no_connect"))
    )
    (net (code "94") (name "unconnected-(M1-PF7-Pad49)") (class "Default")
      (node (ref "M1") (pin "49") (pinfunction "PF7_49") (pintype "input+no_connect"))
    )
    (net (code "95") (name "unconnected-(M1-VBAT-Pad3)") (class "Default")
      (node (ref "M1") (pin "3") (pinfunction "VBAT_3") (pintype "input+no_connect"))
    )
    (net (code "96") (name "unconnected-(M1-VDD-Pad62)") (class "Default")
      (node (ref "M1") (pin "62") (pinfunction "VDD_62") (pintype "input+no_connect"))
    )
    (net (code "97") (name "unconnected-(P1-Pad7)") (class "Default")
      (node (ref "P1") (pin "7") (pinfunction "7_7") (pintype "passive"))
    )
    (net (code "98") (name "unconnected-(P4-Pad4)") (class "Default")
      (node (ref "P4") (pin "4") (pinfunction "4_4") (pintype "passive+no_connect"))
    )
  )
)
